# M4F_MCU_Antennas.net
KiCad netlist of a schematic drawn in Altium Designer
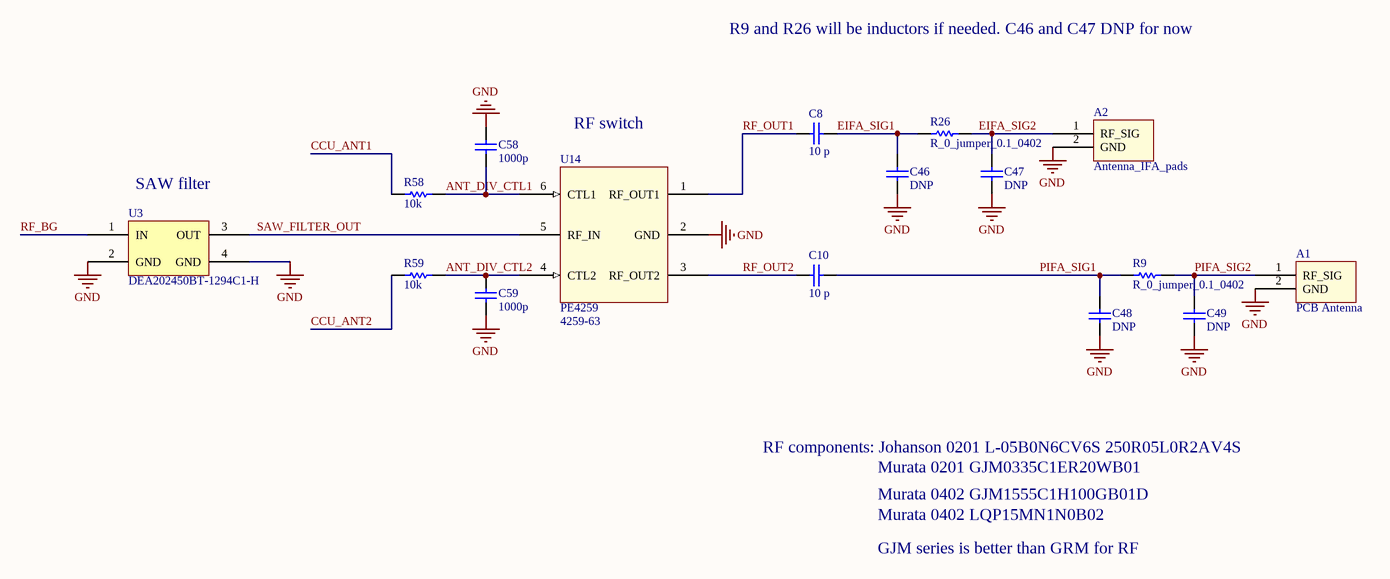
[diagram p0: M4F_MCU_Antennas.SchDoc]

(export (version "E")
  (design (tool "Eeschema 10.0.6"))
  (components
    (comp (ref "A1")
      (value "PCB Antenna")
      (footprint "Antenna_meander_2.4GHz_middle")
      (description "Meander antenna printed on PCB")
      (libsource (lib "Morpheus_pill") (part "Antenna_meander_2.4GHz_middle"))
    )
    (comp (ref "A2")
      (value "Antenna_IFA_pads")
      (footprint "Antenna_Pads")
      (description "PCB pads for external IFA")
      (libsource (lib "Morpheus_pill") (part "Antenna_IFA_pads"))
    )
    (comp (ref "C8")
      (value "10 p")
      (footprint "CAP0402_SENSE_DVT")
      (description "Chip capacitor")
      (fields (field (name "TOLERANCE") "2 %") (field (name "VOLTAGE") "50 V"))
      (libsource (lib "Morpheus_pill") (part "C_10p_2_50_C0G_0402"))
    )
    (comp (ref "C10")
      (value "10 p")
      (footprint "CAP0402_SENSE_DVT")
      (description "Chip capacitor")
      (fields (field (name "TOLERANCE") "2 %") (field (name "VOLTAGE") "50 V"))
      (libsource (lib "Morpheus_pill") (part "C_10p_2_50_C0G_0402"))
    )
    (comp (ref "C46")
      (value "DNP")
      (footprint "CAP0402_SENSE_DVT")
      (description "Chip capacitor")
      (fields (field (name "TOLERANCE") "0.05") (field (name "VOLTAGE") "50 V"))
      (libsource (lib "Morpheus_pill") (part "C_2.2p_0.05_50_C0G_0402"))
    )
    (comp (ref "C47")
      (value "DNP")
      (footprint "CAP0402_SENSE_DVT")
      (description "Chip capacitor")
      (fields (field (name "TOLERANCE") "0.05") (field (name "VOLTAGE") "50 V"))
      (libsource (lib "Morpheus_pill") (part "C_2.2p_0.05_50_C0G_0402"))
    )
    (comp (ref "C48")
      (value "DNP")
      (footprint "CAP0402_SENSE_DVT")
      (description "Chip capacitor")
      (fields (field (name "TOLERANCE") "0.05") (field (name "VOLTAGE") "50 V"))
      (libsource (lib "Morpheus_pill") (part "C_2.2p_0.05_50_C0G_0402"))
    )
    (comp (ref "C49")
      (value "DNP")
      (footprint "CAP0402_SENSE_DVT")
      (description "Chip capacitor")
      (fields (field (name "TOLERANCE") "0.05") (field (name "VOLTAGE") "50 V"))
      (libsource (lib "Morpheus_pill") (part "C_2.2p_0.05_50_C0G_0402"))
    )
    (comp (ref "C58")
      (value "1000p")
      (footprint "CAP0402_SENSE_DVT")
      (description "Chip capacitor")
      (fields (field (name "TOLERANCE") "10%") (field (name "VOLTAGE") "50V"))
      (libsource (lib "Morpheus_pill") (part "C_1000p_10_50_X7R_0402"))
    )
    (comp (ref "C59")
      (value "1000p")
      (footprint "CAP0402_SENSE_DVT")
      (description "Chip capacitor")
      (fields (field (name "TOLERANCE") "10%") (field (name "VOLTAGE") "50V"))
      (libsource (lib "Morpheus_pill") (part "C_1000p_10_50_X7R_0402"))
    )
    (comp (ref "R9")
      (value "R_0_jumper_0.1_0402")
      (footprint "RES0402-SENSE-DVT")
      (description "Chip Resistor")
      (fields (field (name "TOLERANCE") "Jumper") (field (name "POWER") "0.1 W"))
      (libsource (lib "Morpheus_pill") (part "R_0_jumper_0.1_0402"))
    )
    (comp (ref "R26")
      (value "R_0_jumper_0.1_0402")
      (footprint "RES0402-SENSE-DVT")
      (description "Chip Resistor")
      (fields (field (name "TOLERANCE") "Jumper") (field (name "POWER") "0.1 W"))
      (libsource (lib "Morpheus_pill") (part "R_0_jumper_0.1_0402"))
    )
    (comp (ref "R58")
      (value "10k")
      (footprint "RES0402_SENSE_DVT")
      (description "Chip Resistor")
      (fields (field (name "TOLERANCE") "5 %") (field (name "POWER") "0.1 W"))
      (libsource (lib "Morpheus_pill") (part "R_10k_5_0.1_0402"))
    )
    (comp (ref "R59")
      (value "10k")
      (footprint "RES0402_SENSE_DVT")
      (description "Chip Resistor")
      (fields (field (name "TOLERANCE") "5 %") (field (name "POWER") "0.1 W"))
      (libsource (lib "Morpheus_pill") (part "R_10k_5_0.1_0402"))
    )
    (comp (ref "U3")
      (value "DEA202450BT-1294C1-H")
      (footprint "DEA202450BT-1294C1-H")
      (description "SAW filter for 2.4 GHz WLAN")
      (libsource (lib "Morpheus_pill") (part "DEA202450BT-1294C1-H"))
    )
    (comp (ref "U14")
      (value "PE4259")
      (footprint "SOT65P212X110-6N")
      (description "RF Switch")
      (fields (field (name "PN") "4259-63"))
      (libsource (lib "Morpheus_pill") (part "PE4259"))
    )
  )
  (nets
    (net (code "1") (name "/ANT_DIV_CTL1") (class "Default")
      (node (ref "C58") (pin "2") (pinfunction "2_2") (pintype "passive"))
      (node (ref "R58") (pin "2") (pinfunction "2_2") (pintype "passive"))
      (node (ref "U14") (pin "6") (pinfunction "CTL1_6") (pintype "input"))
    )
    (net (code "2") (name "/ANT_DIV_CTL2") (class "Default")
      (node (ref "C59") (pin "2") (pinfunction "2_2") (pintype "passive"))
      (node (ref "R59") (pin "2") (pinfunction "2_2") (pintype "passive"))
      (node (ref "U14") (pin "4") (pinfunction "CTL2_4") (pintype "input"))
    )
    (net (code "3") (name "/CCU_ANT1") (class "Default")
      (node (ref "R58") (pin "1") (pinfunction "1_1") (pintype "passive"))
    )
    (net (code "4") (name "/CCU_ANT2") (class "Default")
      (node (ref "R59") (pin "1") (pinfunction "1_1") (pintype "passive"))
    )
    (net (code "5") (name "/EIFA_SIG1") (class "Default")
      (node (ref "C46") (pin "1") (pinfunction "1_1") (pintype "passive"))
      (node (ref "C8") (pin "2") (pinfunction "2_2") (pintype "passive"))
      (node (ref "R26") (pin "1") (pinfunction "1_1") (pintype "passive"))
    )
    (net (code "6") (name "/EIFA_SIG2") (class "Default")
      (node (ref "A2") (pin "1") (pinfunction "RF_SIG_1") (pintype "passive"))
      (node (ref "C47") (pin "1") (pinfunction "1_1") (pintype "passive"))
      (node (ref "R26") (pin "2") (pinfunction "2_2") (pintype "passive"))
    )
    (net (code "7") (name "/PIFA_SIG1") (class "Default")
      (node (ref "C10") (pin "2") (pinfunction "2_2") (pintype "passive"))
      (node (ref "C48") (pin "1") (pinfunction "1_1") (pintype "passive"))
      (node (ref "R9") (pin "1") (pinfunction "1_1") (pintype "passive"))
    )
    (net (code "8") (name "/PIFA_SIG2") (class "Default")
      (node (ref "A1") (pin "1") (pinfunction "RF_SIG_1") (pintype "passive"))
      (node (ref "C49") (pin "1") (pinfunction "1_1") (pintype "passive"))
      (node (ref "R9") (pin "2") (pinfunction "2_2") (pintype "passive"))
    )
    (net (code "9") (name "/RF_BG") (class "Default")
      (node (ref "U3") (pin "1") (pinfunction "IN_1") (pintype "passive"))
    )
    (net (code "10") (name "/RF_OUT1") (class "Default")
      (node (ref "C8") (pin "1") (pinfunction "1_1") (pintype "passive"))
      (node (ref "U14") (pin "1") (pinfunction "RF_OUT1_1") (pintype "passive"))
    )
    (net (code "11") (name "/RF_OUT2") (class "Default")
      (node (ref "C10") (pin "1") (pinfunction "1_1") (pintype "passive"))
      (node (ref "U14") (pin "3") (pinfunction "RF_OUT2_3") (pintype "passive"))
    )
    (net (code "12") (name "/SAW_FILTER_OUT") (class "Default")
      (node (ref "U14") (pin "5") (pinfunction "RF_IN_5") (pintype "passive"))
      (node (ref "U3") (pin "3") (pinfunction "OUT_3") (pintype "passive"))
    )
    (net (code "13") (name "GND") (class "Default")
      (node (ref "A1") (pin "2") (pinfunction "GND_2") (pintype "passive"))
      (node (ref "A2") (pin "2") (pinfunction "GND_2") (pintype "passive"))
      (node (ref "C46") (pin "2") (pinfunction "2_2") (pintype "passive"))
      (node (ref "C47") (pin "2") (pinfunction "2_2") (pintype "passive"))
      (node (ref "C48") (pin "2") (pinfunction "2_2") (pintype "passive"))
      (node (ref "C49") (pin "2") (pinfunction "2_2") (pintype "passive"))
      (node (ref "C58") (pin "1") (pinfunction "1_1") (pintype "passive"))
      (node (ref "C59") (pin "1") (pinfunction "1_1") (pintype "passive"))
      (node (ref "U14") (pin "2") (pinfunction "GND_2") (pintype "power_in"))
      (node (ref "U3") (pin "2") (pinfunction "GND_2") (pintype "passive"))
      (node (ref "U3") (pin "4") (pinfunction "GND_4") (pintype "passive"))
    )
  )
)
